# MergeRev4_0.net
KiCad netlist of a schematic drawn in Altium Designer
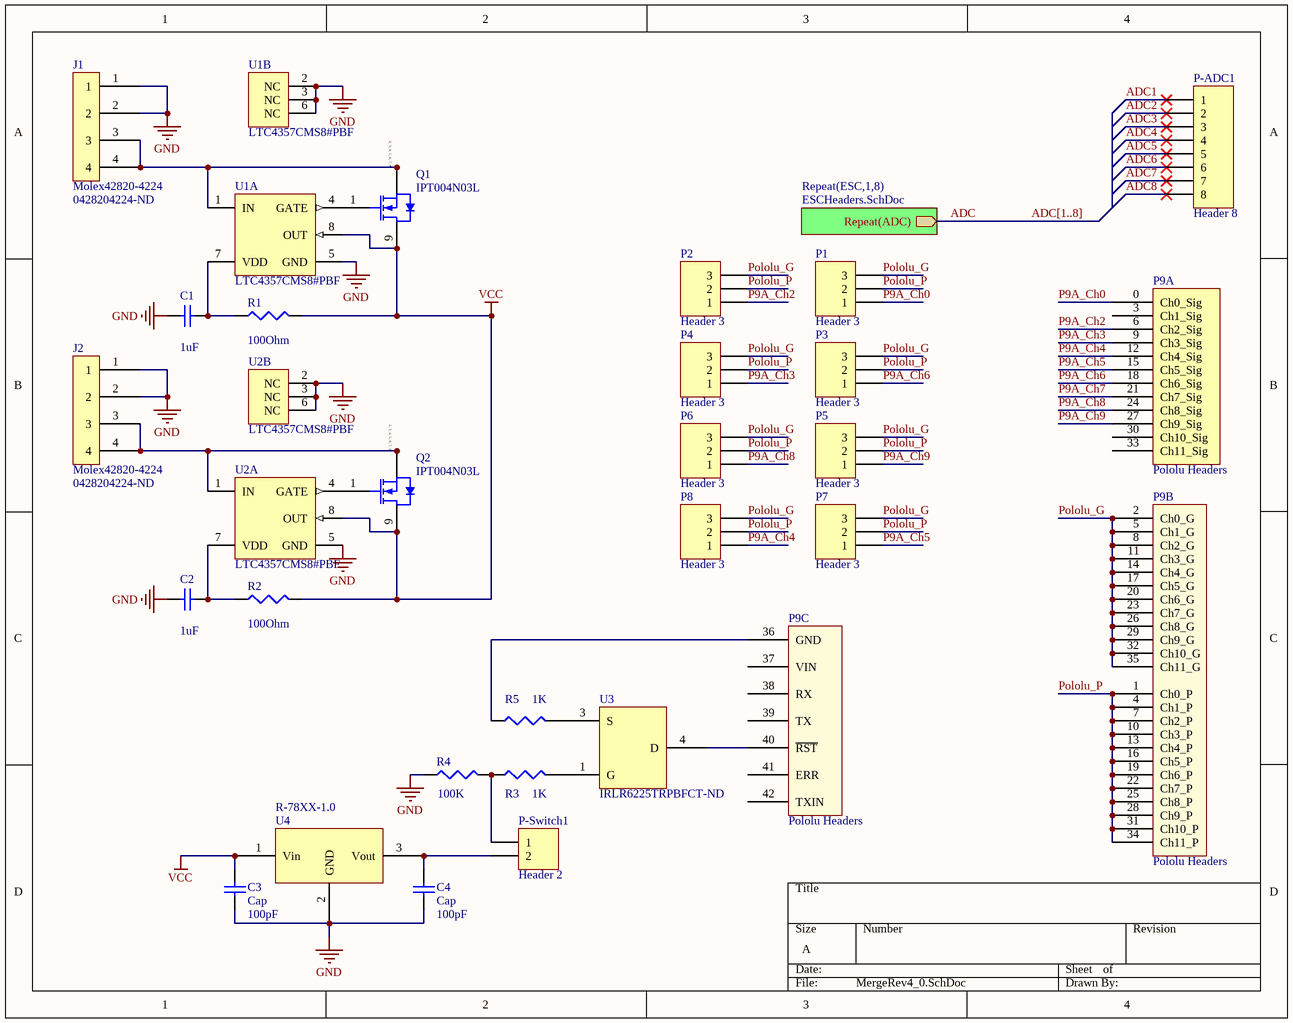
[diagram p0: MergeRev4_0.SchDoc]

(export (version "E")
  (design (tool "Eeschema 10.0.6"))
  (components
    (comp (ref "C1")
      (value "1uF")
      (footprint "C1206")
      (description "Capacitor (Semiconductor SIM Model)")
      (fields (field (name "Comment") "Cap Semi") (field (name "PUBLISHER") "Altium Limited"))
      (libsource (lib "Miscellaneous Devices") (part "Cap Semi"))
    )
    (comp (ref "C2")
      (value "1uF")
      (footprint "C1206")
      (description "Capacitor (Semiconductor SIM Model)")
      (fields (field (name "Comment") "Cap Semi") (field (name "PUBLISHER") "Altium Limited"))
      (libsource (lib "Miscellaneous Devices") (part "Cap Semi"))
    )
    (comp (ref "C3")
      (value "Cap")
      (footprint "1608[0603]")
      (description "Capacitor")
      (fields (field (name "ALTIUM_VALUE") "100pF") (field (name "PUBLISHER") "Altium Limited"))
      (libsource (lib "Miscellaneous Devices") (part "Cap"))
    )
    (comp (ref "C4")
      (value "Cap")
      (footprint "1608[0603]")
      (description "Capacitor")
      (fields (field (name "ALTIUM_VALUE") "100pF") (field (name "PUBLISHER") "Altium Limited"))
      (libsource (lib "Miscellaneous Devices") (part "Cap"))
    )
    (comp (ref "J1")
      (value "Molex42820-4224")
      (footprint "Molex42820-4224")
      (fields (field (name "SUPPLIER PART NUMBER 1") "0428204224-ND"))
      (libsource (lib "Molex42820-4224") (part "Molex42820-4224"))
    )
    (comp (ref "J2")
      (value "Molex42820-4224")
      (footprint "Molex42820-4224")
      (fields (field (name "SUPPLIER PART NUMBER 1") "0428204224-ND"))
      (libsource (lib "Molex42820-4224") (part "Molex42820-4224"))
    )
    (comp (ref "P-ADC1")
      (value "Header 8")
      (footprint "HDR1X8")
      (description "Header, 8-Pin")
      (fields (field (name "PUBLISHER") "Altium Limited"))
      (libsource (lib "Miscellaneous Connectors") (part "Header 8"))
    )
    (comp (ref "P-Switch1")
      (value "Header 2")
      (footprint "HDR1X2")
      (description "Header, 2-Pin")
      (fields (field (name "PUBLISHER") "Altium Limited"))
      (libsource (lib "Miscellaneous Connectors") (part "Header 2"))
    )
    (comp (ref "P1")
      (value "Header 3")
      (footprint "HDR1X3")
      (description "Header, 3-Pin")
      (fields (field (name "PUBLISHER") "Altium Limited"))
      (libsource (lib "Miscellaneous Connectors") (part "Header 3"))
    )
    (comp (ref "P2")
      (value "Header 3")
      (footprint "HDR1X3")
      (description "Header, 3-Pin")
      (fields (field (name "PUBLISHER") "Altium Limited"))
      (libsource (lib "Miscellaneous Connectors") (part "Header 3"))
    )
    (comp (ref "P3")
      (value "Header 3")
      (footprint "HDR1X3")
      (description "Header, 3-Pin")
      (fields (field (name "PUBLISHER") "Altium Limited"))
      (libsource (lib "Miscellaneous Connectors") (part "Header 3"))
    )
    (comp (ref "P4")
      (value "Header 3")
      (footprint "HDR1X3")
      (description "Header, 3-Pin")
      (fields (field (name "PUBLISHER") "Altium Limited"))
      (libsource (lib "Miscellaneous Connectors") (part "Header 3"))
    )
    (comp (ref "P5")
      (value "Header 3")
      (footprint "HDR1X3")
      (description "Header, 3-Pin")
      (fields (field (name "PUBLISHER") "Altium Limited"))
      (libsource (lib "Miscellaneous Connectors") (part "Header 3"))
    )
    (comp (ref "P6")
      (value "Header 3")
      (footprint "HDR1X3")
      (description "Header, 3-Pin")
      (fields (field (name "PUBLISHER") "Altium Limited"))
      (libsource (lib "Miscellaneous Connectors") (part "Header 3"))
    )
    (comp (ref "P7")
      (value "Header 3")
      (footprint "HDR1X3")
      (description "Header, 3-Pin")
      (fields (field (name "PUBLISHER") "Altium Limited"))
      (libsource (lib "Miscellaneous Connectors") (part "Header 3"))
    )
    (comp (ref "P8")
      (value "Header 3")
      (footprint "HDR1X3")
      (description "Header, 3-Pin")
      (fields (field (name "PUBLISHER") "Altium Limited"))
      (libsource (lib "Miscellaneous Connectors") (part "Header 3"))
    )
    (comp (ref "P9")
      (value "Pololu Headers")
      (footprint "Pololu Headers")
      (libsource (lib "MergeRev3_0") (part "Pololu Headers"))
    )
    (comp (ref "Q1")
      (value "IPT004N03L")
      (footprint "INF-PG-HSOF-8-1_V")
      (description "N-Channel OptiMOS(TM) Power-MOSFET, 30 V VDS, 300 A ID, -55 to 175 degC, PG-HSOF-8, Reel, Green")
      (fields (field (name "MANUFACTURER") "Infineon"))
      (libsource (lib "MergeRev3_0") (part "IPT004N03L"))
    )
    (comp (ref "Q2")
      (value "IPT004N03L")
      (footprint "INF-PG-HSOF-8-1_V")
      (description "N-Channel OptiMOS(TM) Power-MOSFET, 30 V VDS, 300 A ID, -55 to 175 degC, PG-HSOF-8, Reel, Green")
      (fields (field (name "MANUFACTURER") "Infineon"))
      (libsource (lib "MergeRev3_0") (part "IPT004N03L"))
    )
    (comp (ref "R1")
      (value "100Ohm")
      (footprint "J1-0603")
      (description "Resistor")
      (fields (field (name "Comment") "Res3") (field (name "PUBLISHER") "Altium Limited"))
      (libsource (lib "Miscellaneous Devices") (part "Res3"))
    )
    (comp (ref "R2")
      (value "100Ohm")
      (footprint "J1-0603")
      (description "Resistor")
      (fields (field (name "Comment") "Res3") (field (name "PUBLISHER") "Altium Limited"))
      (libsource (lib "Miscellaneous Devices") (part "Res3"))
    )
    (comp (ref "R3")
      (value "1K")
      (footprint "J1-0603")
      (description "Resistor")
      (fields (field (name "Comment") "Res3") (field (name "PUBLISHER") "Altium Limited"))
      (libsource (lib "Miscellaneous Devices") (part "Res3"))
    )
    (comp (ref "R4")
      (value "100K")
      (footprint "J1-0603")
      (description "Resistor")
      (fields (field (name "Comment") "Res3") (field (name "PUBLISHER") "Altium Limited"))
      (libsource (lib "Miscellaneous Devices") (part "Res3"))
    )
    (comp (ref "R5")
      (value "1K")
      (footprint "J1-0603")
      (description "Resistor")
      (fields (field (name "Comment") "Res3") (field (name "PUBLISHER") "Altium Limited"))
      (libsource (lib "Miscellaneous Devices") (part "Res3"))
    )
    (comp (ref "U1")
      (value "LTC4357CMS8#PBF")
      (footprint "LT-MS8-8_N")
      (fields (field (name "MANUFACTURER") "Linear Technology"))
      (libsource (lib "MergeRev3_0") (part "LTC4357CMS8#PBF"))
    )
    (comp (ref "U2")
      (value "LTC4357CMS8#PBF")
      (footprint "LT-MS8-8_N")
      (fields (field (name "MANUFACTURER") "Linear Technology"))
      (libsource (lib "MergeRev3_0") (part "LTC4357CMS8#PBF"))
    )
    (comp (ref "U3")
      (value "IRLR6225TRPBFCT-ND")
      (footprint "IRLR6225_DT")
      (libsource (lib "IRLR6225_DT") (part "IRLR6225TRPBFCT-ND"))
    )
    (comp (ref "U4")
      (value "R-78XX-1.0")
      (footprint "R-785.0-1.0")
      (libsource (lib "RECOM-Reg") (part "R-78XX-1.0"))
    )
  )
  (nets
    (net (code "2") (name "/ADC1") (class "Default")
      (node (ref "P-ADC1") (pin "1") (pinfunction "1_1") (pintype "passive+no_connect"))
    )
    (net (code "3") (name "/ADC2") (class "Default")
      (node (ref "P-ADC1") (pin "2") (pinfunction "2_2") (pintype "passive+no_connect"))
    )
    (net (code "4") (name "/ADC3") (class "Default")
      (node (ref "P-ADC1") (pin "3") (pinfunction "3_3") (pintype "passive+no_connect"))
    )
    (net (code "5") (name "/ADC4") (class "Default")
      (node (ref "P-ADC1") (pin "4") (pinfunction "4_4") (pintype "passive+no_connect"))
    )
    (net (code "6") (name "/ADC5") (class "Default")
      (node (ref "P-ADC1") (pin "5") (pinfunction "5_5") (pintype "passive+no_connect"))
    )
    (net (code "7") (name "/ADC6") (class "Default")
      (node (ref "P-ADC1") (pin "6") (pinfunction "6_6") (pintype "passive+no_connect"))
    )
    (net (code "8") (name "/ADC7") (class "Default")
      (node (ref "P-ADC1") (pin "7") (pinfunction "7_7") (pintype "passive+no_connect"))
    )
    (net (code "9") (name "/ADC8") (class "Default")
      (node (ref "P-ADC1") (pin "8") (pinfunction "8_8") (pintype "passive+no_connect"))
    )
    (net (code "11") (name "/P9A_Ch0") (class "Default")
      (node (ref "P1") (pin "1") (pinfunction "1_1") (pintype "passive"))
      (node (ref "P9") (pin "0") (pinfunction "Ch0_Sig_0") (pintype "passive"))
    )
    (net (code "12") (name "/P9A_Ch2") (class "Default")
      (node (ref "P2") (pin "1") (pinfunction "1_1") (pintype "passive"))
      (node (ref "P9") (pin "6") (pinfunction "Ch2_Sig_6") (pintype "passive"))
    )
    (net (code "13") (name "/P9A_Ch3") (class "Default")
      (node (ref "P4") (pin "1") (pinfunction "1_1") (pintype "passive"))
      (node (ref "P9") (pin "9") (pinfunction "Ch3_Sig_9") (pintype "passive"))
    )
    (net (code "14") (name "/P9A_Ch4") (class "Default")
      (node (ref "P8") (pin "1") (pinfunction "1_1") (pintype "passive"))
      (node (ref "P9") (pin "12") (pinfunction "Ch4_Sig_12") (pintype "passive"))
    )
    (net (code "15") (name "/P9A_Ch5") (class "Default")
      (node (ref "P7") (pin "1") (pinfunction "1_1") (pintype "passive"))
      (node (ref "P9") (pin "15") (pinfunction "Ch5_Sig_15") (pintype "passive"))
    )
    (net (code "16") (name "/P9A_Ch6") (class "Default")
      (node (ref "P3") (pin "1") (pinfunction "1_1") (pintype "passive"))
      (node (ref "P9") (pin "18") (pinfunction "Ch6_Sig_18") (pintype "passive"))
    )
    (net (code "17") (name "/P9A_Ch7") (class "Default")
      (node (ref "P9") (pin "21") (pinfunction "Ch7_Sig_21") (pintype "passive"))
    )
    (net (code "18") (name "/P9A_Ch8") (class "Default")
      (node (ref "P6") (pin "1") (pinfunction "1_1") (pintype "passive"))
      (node (ref "P9") (pin "24") (pinfunction "Ch8_Sig_24") (pintype "passive"))
    )
    (net (code "19") (name "/P9A_Ch9") (class "Default")
      (node (ref "P5") (pin "1") (pinfunction "1_1") (pintype "passive"))
      (node (ref "P9") (pin "27") (pinfunction "Ch9_Sig_27") (pintype "passive"))
    )
    (net (code "20") (name "/Pololu_G") (class "Default")
      (node (ref "P1") (pin "3") (pinfunction "3_3") (pintype "passive"))
      (node (ref "P2") (pin "3") (pinfunction "3_3") (pintype "passive"))
      (node (ref "P3") (pin "3") (pinfunction "3_3") (pintype "passive"))
      (node (ref "P4") (pin "3") (pinfunction "3_3") (pintype "passive"))
      (node (ref "P5") (pin "3") (pinfunction "3_3") (pintype "passive"))
      (node (ref "P6") (pin "3") (pinfunction "3_3") (pintype "passive"))
      (node (ref "P7") (pin "3") (pinfunction "3_3") (pintype "passive"))
      (node (ref "P8") (pin "3") (pinfunction "3_3") (pintype "passive"))
      (node (ref "P9") (pin "11") (pinfunction "Ch3_G_11") (pintype "passive"))
      (node (ref "P9") (pin "14") (pinfunction "Ch4_G_14") (pintype "passive"))
      (node (ref "P9") (pin "17") (pinfunction "Ch5_G_17") (pintype "passive"))
      (node (ref "P9") (pin "2") (pinfunction "Ch0_G_2") (pintype "passive"))
      (node (ref "P9") (pin "20") (pinfunction "Ch6_G_20") (pintype "passive"))
      (node (ref "P9") (pin "23") (pinfunction "Ch7_G_23") (pintype "passive"))
      (node (ref "P9") (pin "26") (pinfunction "Ch8_G_26") (pintype "passive"))
      (node (ref "P9") (pin "29") (pinfunction "Ch9_G_29") (pintype "passive"))
      (node (ref "P9") (pin "32") (pinfunction "Ch10_G_32") (pintype "passive"))
      (node (ref "P9") (pin "35") (pinfunction "Ch11_G_35") (pintype "passive"))
      (node (ref "P9") (pin "5") (pinfunction "Ch1_G_5") (pintype "passive"))
      (node (ref "P9") (pin "8") (pinfunction "Ch2_G_8") (pintype "passive"))
    )
    (net (code "21") (name "/Pololu_P") (class "Default")
      (node (ref "P1") (pin "2") (pinfunction "2_2") (pintype "passive"))
      (node (ref "P2") (pin "2") (pinfunction "2_2") (pintype "passive"))
      (node (ref "P3") (pin "2") (pinfunction "2_2") (pintype "passive"))
      (node (ref "P4") (pin "2") (pinfunction "2_2") (pintype "passive"))
      (node (ref "P5") (pin "2") (pinfunction "2_2") (pintype "passive"))
      (node (ref "P6") (pin "2") (pinfunction "2_2") (pintype "passive"))
      (node (ref "P7") (pin "2") (pinfunction "2_2") (pintype "passive"))
      (node (ref "P8") (pin "2") (pinfunction "2_2") (pintype "passive"))
      (node (ref "P9") (pin "1") (pinfunction "Ch0_P_1") (pintype "passive"))
      (node (ref "P9") (pin "10") (pinfunction "Ch3_P_10") (pintype "passive"))
      (node (ref "P9") (pin "13") (pinfunction "Ch4_P_13") (pintype "passive"))
      (node (ref "P9") (pin "16") (pinfunction "Ch5_P_16") (pintype "passive"))
      (node (ref "P9") (pin "19") (pinfunction "Ch6_P_19") (pintype "passive"))
      (node (ref "P9") (pin "22") (pinfunction "Ch7_P_22") (pintype "passive"))
      (node (ref "P9") (pin "25") (pinfunction "Ch8_P_25") (pintype "passive"))
      (node (ref "P9") (pin "28") (pinfunction "Ch9_P_28") (pintype "passive"))
      (node (ref "P9") (pin "31") (pinfunction "Ch10_P_31") (pintype "passive"))
      (node (ref "P9") (pin "34") (pinfunction "Ch11_P_34") (pintype "passive"))
      (node (ref "P9") (pin "4") (pinfunction "Ch1_P_4") (pintype "passive"))
      (node (ref "P9") (pin "7") (pinfunction "Ch2_P_7") (pintype "passive"))
    )
    (net (code "22") (name "GND") (class "Default")
      (node (ref "C1") (pin "1") (pinfunction "1_1") (pintype "passive"))
      (node (ref "C2") (pin "1") (pinfunction "1_1") (pintype "passive"))
      (node (ref "C3") (pin "1") (pinfunction "1_1") (pintype "passive"))
      (node (ref "C4") (pin "1") (pinfunction "1_1") (pintype "passive"))
      (node (ref "J1") (pin "1") (pinfunction "1_1") (pintype "power_in"))
      (node (ref "J1") (pin "2") (pinfunction "2_2") (pintype "power_in"))
      (node (ref "J2") (pin "1") (pinfunction "1_1") (pintype "power_in"))
      (node (ref "J2") (pin "2") (pinfunction "2_2") (pintype "power_in"))
      (node (ref "R4") (pin "1") (pinfunction "1_1") (pintype "passive"))
      (node (ref "U1") (pin "2") (pinfunction "NC_2") (pintype "passive"))
      (node (ref "U1") (pin "3") (pinfunction "NC_3") (pintype "passive"))
      (node (ref "U1") (pin "5") (pinfunction "GND_5") (pintype "power_in"))
      (node (ref "U1") (pin "6") (pinfunction "NC_6") (pintype "passive"))
      (node (ref "U2") (pin "2") (pinfunction "NC_2") (pintype "passive"))
      (node (ref "U2") (pin "3") (pinfunction "NC_3") (pintype "passive"))
      (node (ref "U2") (pin "5") (pinfunction "GND_5") (pintype "power_in"))
      (node (ref "U2") (pin "6") (pinfunction "NC_6") (pintype "passive"))
      (node (ref "U4") (pin "2") (pinfunction "GND_2") (pintype "passive"))
    )
    (net (code "23") (name "Net-(P-Switch1-Pad1)") (class "Default")
      (node (ref "P-Switch1") (pin "1") (pinfunction "1_1") (pintype "passive"))
      (node (ref "R3") (pin "1") (pinfunction "1_1") (pintype "passive"))
      (node (ref "R4") (pin "2") (pinfunction "2_2") (pintype "passive"))
    )
    (net (code "24") (name "Net-(P9C-GND)") (class "Default")
      (node (ref "P9") (pin "36") (pinfunction "GND_36") (pintype "passive"))
      (node (ref "R5") (pin "1") (pinfunction "1_1") (pintype "passive"))
    )
    (net (code "25") (name "Net-(P9C-~{RST})") (class "Default")
      (node (ref "P9") (pin "40") (pinfunction "~{RST}_40") (pintype "passive"))
      (node (ref "U3") (pin "4") (pinfunction "D_4") (pintype "passive"))
    )
    (net (code "26") (name "Net-(Q1-GATE)") (class "Default")
      (node (ref "Q1") (pin "1") (pinfunction "GATE_1") (pintype "passive"))
      (node (ref "U1") (pin "4") (pinfunction "GATE_4") (pintype "output"))
    )
    (net (code "27") (name "Net-(Q2-GATE)") (class "Default")
      (node (ref "Q2") (pin "1") (pinfunction "GATE_1") (pintype "passive"))
      (node (ref "U2") (pin "4") (pinfunction "GATE_4") (pintype "output"))
    )
    (net (code "28") (name "Net-(U1A-IN)") (class "Default")
      (node (ref "J1") (pin "3") (pinfunction "3_3") (pintype "power_in"))
      (node (ref "J1") (pin "4") (pinfunction "4_4") (pintype "power_in"))
      (node (ref "Q1") (pin "2") (pinfunction "S_2") (pintype "passive"))
      (node (ref "Q1") (pin "3") (pinfunction "S_3") (pintype "passive"))
      (node (ref "Q1") (pin "4") (pinfunction "S_4") (pintype "passive"))
      (node (ref "Q1") (pin "5") (pinfunction "S_5") (pintype "passive"))
      (node (ref "Q1") (pin "6") (pinfunction "S_6") (pintype "passive"))
      (node (ref "Q1") (pin "7") (pinfunction "S_7") (pintype "passive"))
      (node (ref "Q1") (pin "8") (pinfunction "S_8") (pintype "passive"))
      (node (ref "U1") (pin "1") (pinfunction "IN_1") (pintype "power_in"))
    )
    (net (code "29") (name "Net-(U1A-VDD)") (class "Default")
      (node (ref "C1") (pin "2") (pinfunction "2_2") (pintype "passive"))
      (node (ref "R1") (pin "1") (pinfunction "1_1") (pintype "passive"))
      (node (ref "U1") (pin "7") (pinfunction "VDD_7") (pintype "power_in"))
    )
    (net (code "30") (name "Net-(U2A-IN)") (class "Default")
      (node (ref "J2") (pin "3") (pinfunction "3_3") (pintype "power_in"))
      (node (ref "J2") (pin "4") (pinfunction "4_4") (pintype "power_in"))
      (node (ref "Q2") (pin "2") (pinfunction "S_2") (pintype "passive"))
      (node (ref "Q2") (pin "3") (pinfunction "S_3") (pintype "passive"))
      (node (ref "Q2") (pin "4") (pinfunction "S_4") (pintype "passive"))
      (node (ref "Q2") (pin "5") (pinfunction "S_5") (pintype "passive"))
      (node (ref "Q2") (pin "6") (pinfunction "S_6") (pintype "passive"))
      (node (ref "Q2") (pin "7") (pinfunction "S_7") (pintype "passive"))
      (node (ref "Q2") (pin "8") (pinfunction "S_8") (pintype "passive"))
      (node (ref "U2") (pin "1") (pinfunction "IN_1") (pintype "power_in"))
    )
    (net (code "31") (name "Net-(U2A-VDD)") (class "Default")
      (node (ref "C2") (pin "2") (pinfunction "2_2") (pintype "passive"))
      (node (ref "R2") (pin "1") (pinfunction "1_1") (pintype "passive"))
      (node (ref "U2") (pin "7") (pinfunction "VDD_7") (pintype "power_in"))
    )
    (net (code "32") (name "Net-(U3-G)") (class "Default")
      (node (ref "R3") (pin "2") (pinfunction "2_2") (pintype "passive"))
      (node (ref "U3") (pin "1") (pinfunction "G_1") (pintype "passive"))
    )
    (net (code "33") (name "Net-(U3-S)") (class "Default")
      (node (ref "R5") (pin "2") (pinfunction "2_2") (pintype "passive"))
      (node (ref "U3") (pin "3") (pinfunction "S_3") (pintype "passive"))
    )
    (net (code "34") (name "Net-(U4-Vout)") (class "Default")
      (node (ref "C4") (pin "2") (pinfunction "2_2") (pintype "passive"))
      (node (ref "P-Switch1") (pin "2") (pinfunction "2_2") (pintype "passive"))
      (node (ref "U4") (pin "3") (pinfunction "Vout_3") (pintype "passive"))
    )
    (net (code "35") (name "VCC") (class "Default")
      (node (ref "C3") (pin "2") (pinfunction "2_2") (pintype "passive"))
      (node (ref "Q1") (pin "9") (pinfunction "D_9") (pintype "passive"))
      (node (ref "Q2") (pin "9") (pinfunction "D_9") (pintype "passive"))
      (node (ref "R1") (pin "2") (pinfunction "2_2") (pintype "passive"))
      (node (ref "R2") (pin "2") (pinfunction "2_2") (pintype "passive"))
      (node (ref "U1") (pin "8") (pinfunction "OUT_8") (pintype "input"))
      (node (ref "U2") (pin "8") (pinfunction "OUT_8") (pintype "input"))
      (node (ref "U4") (pin "1") (pinfunction "Vin_1") (pintype "passive"))
    )
    (net (code "36") (name "unconnected-(P9A-Ch1_Sig-Pad3)") (class "Default")
      (node (ref "P9") (pin "3") (pinfunction "Ch1_Sig_3") (pintype "passive"))
    )
    (net (code "37") (name "unconnected-(P9A-Ch10_Sig-Pad30)") (class "Default")
      (node (ref "P9") (pin "30") (pinfunction "Ch10_Sig_30") (pintype "passive"))
    )
    (net (code "38") (name "unconnected-(P9A-Ch11_Sig-Pad33)") (class "Default")
      (node (ref "P9") (pin "33") (pinfunction "Ch11_Sig_33") (pintype "passive"))
    )
    (net (code "39") (name "unconnected-(P9C-ERR-Pad41)") (class "Default")
      (node (ref "P9") (pin "41") (pinfunction "ERR_41") (pintype "passive"))
    )
    (net (code "40") (name "unconnected-(P9C-RX-Pad38)") (class "Default")
      (node (ref "P9") (pin "38") (pinfunction "RX_38") (pintype "passive"))
    )
    (net (code "41") (name "unconnected-(P9C-TX-Pad39)") (class "Default")
      (node (ref "P9") (pin "39") (pinfunction "TX_39") (pintype "passive"))
    )
    (net (code "42") (name "unconnected-(P9C-TXIN-Pad42)") (class "Default")
      (node (ref "P9") (pin "42") (pinfunction "TXIN_42") (pintype "passive"))
    )
    (net (code "43") (name "unconnected-(P9C-VIN-Pad37)") (class "Default")
      (node (ref "P9") (pin "37") (pinfunction "VIN_37") (pintype "passive"))
    )
  )
)
